# Schematic_Thesis.net
KiCad netlist of a schematic drawn in Altium Designer
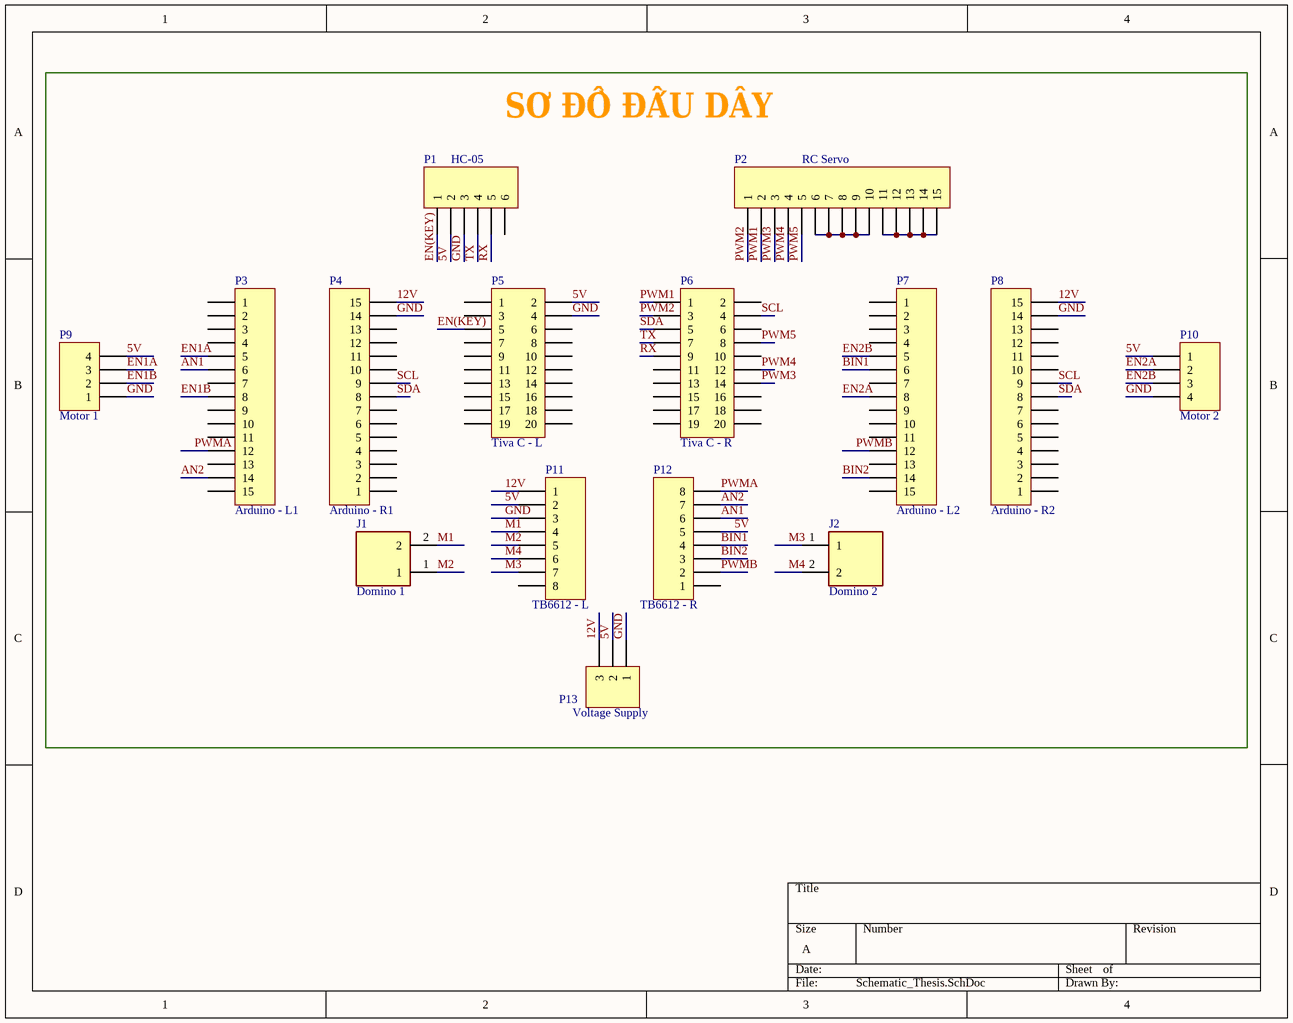
[diagram p0: Schematic_Thesis.SchDoc]

(export (version "E")
  (design (tool "Eeschema 10.0.6"))
  (components
    (comp (ref "J1")
      (value "Domino 1")
      (footprint "KF301-2P:HANDSON_KF301-2P")
      (description "2 Pin Terminal Block 5mm Pitch")
      (fields (field (name "MP") "KF301-2P") (field (name "MF") "Handson Technology"))
      (libsource (lib "") (part "KF301-2P_1"))
    )
    (comp (ref "J2")
      (value "Domino 2")
      (footprint "KF301-2P:HANDSON_KF301-2P")
      (description "2 Pin Terminal Block 5mm Pitch")
      (fields (field (name "MP") "KF301-2P") (field (name "MF") "Handson Technology"))
      (libsource (lib "KF301-2P") (part "KF301-2P"))
    )
    (comp (ref "P1")
      (value "HC-05")
      (footprint "HDR1X6")
      (description "Header, 6-Pin")
      (fields (field (name "PUBLISHER") "Altium Limited"))
      (libsource (lib "Miscellaneous Connectors") (part "Header 6"))
    )
    (comp (ref "P2")
      (value "RC Servo")
      (footprint "HDR1X15")
      (description "Header, 15-Pin")
      (fields (field (name "PUBLISHER") "Altium Limited"))
      (libsource (lib "") (part "Header 15_2"))
    )
    (comp (ref "P3")
      (value "Arduino - L1")
      (footprint "HDR1X15")
      (description "Header, 15-Pin")
      (fields (field (name "PUBLISHER") "Altium Limited"))
      (libsource (lib "Miscellaneous Connectors") (part "Header 15"))
    )
    (comp (ref "P4")
      (value "Arduino - R1")
      (footprint "HDR1X15")
      (description "Header, 15-Pin")
      (fields (field (name "PUBLISHER") "Altium Limited"))
      (libsource (lib "") (part "Header 15_1"))
    )
    (comp (ref "P5")
      (value "Tiva C - L")
      (footprint "HDR2X10")
      (description "Header, 10-Pin, Dual row")
      (fields (field (name "PUBLISHER") "Altium Limited"))
      (libsource (lib "Miscellaneous Connectors") (part "Header 10X2"))
    )
    (comp (ref "P6")
      (value "Tiva C - R")
      (footprint "HDR2X10")
      (description "Header, 10-Pin, Dual row")
      (fields (field (name "PUBLISHER") "Altium Limited"))
      (libsource (lib "Miscellaneous Connectors") (part "Header 10X2"))
    )
    (comp (ref "P7")
      (value "Arduino - L2")
      (footprint "HDR1X15")
      (description "Header, 15-Pin")
      (fields (field (name "PUBLISHER") "Altium Limited"))
      (libsource (lib "Miscellaneous Connectors") (part "Header 15"))
    )
    (comp (ref "P8")
      (value "Arduino - R2")
      (footprint "HDR1X15")
      (description "Header, 15-Pin")
      (fields (field (name "PUBLISHER") "Altium Limited"))
      (libsource (lib "") (part "Header 15_1"))
    )
    (comp (ref "P9")
      (value "Motor 1")
      (footprint "HDR1X4")
      (description "Header, 4-Pin")
      (fields (field (name "PUBLISHER") "Altium Limited"))
      (libsource (lib "Miscellaneous Connectors") (part "Header 4"))
    )
    (comp (ref "P10")
      (value "Motor 2")
      (footprint "HDR1X4")
      (description "Header, 4-Pin")
      (fields (field (name "PUBLISHER") "Altium Limited"))
      (libsource (lib "") (part "Header 4_1"))
    )
    (comp (ref "P11")
      (value "TB6612 - L")
      (footprint "HDR1X8")
      (description "Header, 8-Pin")
      (fields (field (name "PUBLISHER") "Altium Limited"))
      (libsource (lib "") (part "Header 8_1"))
    )
    (comp (ref "P12")
      (value "TB6612 - R")
      (footprint "HDR1X8")
      (description "Header, 8-Pin")
      (fields (field (name "PUBLISHER") "Altium Limited"))
      (libsource (lib "Miscellaneous Connectors") (part "Header 8"))
    )
    (comp (ref "P13")
      (value "Voltage Supply")
      (footprint "HDR1X3")
      (description "Header, 3-Pin")
      (fields (field (name "PUBLISHER") "Altium Limited"))
      (libsource (lib "Miscellaneous Connectors") (part "Header 3"))
    )
  )
  (nets
    (net (code "1") (name "/5V") (class "Default")
      (node (ref "P1") (pin "2") (pinfunction "2_2") (pintype "passive"))
      (node (ref "P10") (pin "1") (pinfunction "1_1") (pintype "passive"))
      (node (ref "P11") (pin "2") (pinfunction "2_2") (pintype "passive"))
      (node (ref "P12") (pin "5") (pinfunction "5_5") (pintype "passive"))
      (node (ref "P13") (pin "2") (pinfunction "2_2") (pintype "passive"))
      (node (ref "P5") (pin "2") (pinfunction "2_2") (pintype "passive"))
      (node (ref "P9") (pin "4") (pinfunction "4_4") (pintype "passive"))
    )
    (net (code "2") (name "/12V") (class "Default")
      (node (ref "P11") (pin "1") (pinfunction "1_1") (pintype "passive"))
      (node (ref "P13") (pin "3") (pinfunction "3_3") (pintype "passive"))
      (node (ref "P4") (pin "15") (pinfunction "15_15") (pintype "passive"))
      (node (ref "P8") (pin "15") (pinfunction "15_15") (pintype "passive"))
    )
    (net (code "3") (name "/AN1") (class "Default")
      (node (ref "P12") (pin "6") (pinfunction "6_6") (pintype "passive"))
      (node (ref "P3") (pin "6") (pinfunction "6_6") (pintype "passive"))
    )
    (net (code "4") (name "/AN2") (class "Default")
      (node (ref "P12") (pin "7") (pinfunction "7_7") (pintype "passive"))
      (node (ref "P3") (pin "14") (pinfunction "14_14") (pintype "passive"))
    )
    (net (code "5") (name "/BIN1") (class "Default")
      (node (ref "P12") (pin "4") (pinfunction "4_4") (pintype "passive"))
      (node (ref "P7") (pin "6") (pinfunction "6_6") (pintype "passive"))
    )
    (net (code "6") (name "/BIN2") (class "Default")
      (node (ref "P12") (pin "3") (pinfunction "3_3") (pintype "passive"))
      (node (ref "P7") (pin "14") (pinfunction "14_14") (pintype "passive"))
    )
    (net (code "7") (name "/EN(KEY)") (class "Default")
      (node (ref "P1") (pin "1") (pinfunction "1_1") (pintype "passive"))
      (node (ref "P5") (pin "5") (pinfunction "5_5") (pintype "passive"))
    )
    (net (code "8") (name "/EN1A") (class "Default")
      (node (ref "P3") (pin "5") (pinfunction "5_5") (pintype "passive"))
      (node (ref "P9") (pin "3") (pinfunction "3_3") (pintype "passive"))
    )
    (net (code "9") (name "/EN1B") (class "Default")
      (node (ref "P3") (pin "8") (pinfunction "8_8") (pintype "passive"))
      (node (ref "P9") (pin "2") (pinfunction "2_2") (pintype "passive"))
    )
    (net (code "10") (name "/EN2A") (class "Default")
      (node (ref "P10") (pin "2") (pinfunction "2_2") (pintype "passive"))
      (node (ref "P7") (pin "8") (pinfunction "8_8") (pintype "passive"))
    )
    (net (code "11") (name "/EN2B") (class "Default")
      (node (ref "P10") (pin "3") (pinfunction "3_3") (pintype "passive"))
      (node (ref "P7") (pin "5") (pinfunction "5_5") (pintype "passive"))
    )
    (net (code "12") (name "/GND") (class "Default")
      (node (ref "P1") (pin "3") (pinfunction "3_3") (pintype "passive"))
      (node (ref "P10") (pin "4") (pinfunction "4_4") (pintype "passive"))
      (node (ref "P11") (pin "3") (pinfunction "3_3") (pintype "passive"))
      (node (ref "P13") (pin "1") (pinfunction "1_1") (pintype "passive"))
      (node (ref "P4") (pin "14") (pinfunction "14_14") (pintype "passive"))
      (node (ref "P5") (pin "4") (pinfunction "4_4") (pintype "passive"))
      (node (ref "P8") (pin "14") (pinfunction "14_14") (pintype "passive"))
      (node (ref "P9") (pin "1") (pinfunction "1_1") (pintype "passive"))
    )
    (net (code "13") (name "/M1") (class "Default")
      (node (ref "J1") (pin "2") (pinfunction "2_2") (pintype "passive"))
      (node (ref "P11") (pin "4") (pinfunction "4_4") (pintype "passive"))
    )
    (net (code "14") (name "/M2") (class "Default")
      (node (ref "J1") (pin "1") (pinfunction "1_1") (pintype "passive"))
      (node (ref "P11") (pin "5") (pinfunction "5_5") (pintype "passive"))
    )
    (net (code "15") (name "/M3") (class "Default")
      (node (ref "J2") (pin "1") (pinfunction "1_1") (pintype "passive"))
      (node (ref "P11") (pin "7") (pinfunction "7_7") (pintype "passive"))
    )
    (net (code "16") (name "/M4") (class "Default")
      (node (ref "J2") (pin "2") (pinfunction "2_2") (pintype "passive"))
      (node (ref "P11") (pin "6") (pinfunction "6_6") (pintype "passive"))
    )
    (net (code "17") (name "/PWM1") (class "Default")
      (node (ref "P2") (pin "2") (pinfunction "2_2") (pintype "passive"))
      (node (ref "P6") (pin "1") (pinfunction "1_1") (pintype "passive"))
    )
    (net (code "18") (name "/PWM2") (class "Default")
      (node (ref "P2") (pin "1") (pinfunction "1_1") (pintype "passive"))
      (node (ref "P6") (pin "3") (pinfunction "3_3") (pintype "passive"))
    )
    (net (code "19") (name "/PWM3") (class "Default")
      (node (ref "P2") (pin "3") (pinfunction "3_3") (pintype "passive"))
      (node (ref "P6") (pin "14") (pinfunction "14_14") (pintype "passive"))
    )
    (net (code "20") (name "/PWM4") (class "Default")
      (node (ref "P2") (pin "4") (pinfunction "4_4") (pintype "passive"))
      (node (ref "P6") (pin "12") (pinfunction "12_12") (pintype "passive"))
    )
    (net (code "21") (name "/PWM5") (class "Default")
      (node (ref "P2") (pin "5") (pinfunction "5_5") (pintype "passive"))
      (node (ref "P6") (pin "8") (pinfunction "8_8") (pintype "passive"))
    )
    (net (code "22") (name "/PWMA") (class "Default")
      (node (ref "P12") (pin "8") (pinfunction "8_8") (pintype "passive"))
      (node (ref "P3") (pin "12") (pinfunction "12_12") (pintype "passive"))
    )
    (net (code "23") (name "/PWMB") (class "Default")
      (node (ref "P12") (pin "2") (pinfunction "2_2") (pintype "passive"))
      (node (ref "P7") (pin "12") (pinfunction "12_12") (pintype "passive"))
    )
    (net (code "24") (name "/RX") (class "Default")
      (node (ref "P1") (pin "5") (pinfunction "5_5") (pintype "passive"))
      (node (ref "P6") (pin "9") (pinfunction "9_9") (pintype "passive"))
    )
    (net (code "25") (name "/SCL") (class "Default")
      (node (ref "P4") (pin "9") (pinfunction "9_9") (pintype "passive"))
      (node (ref "P6") (pin "4") (pinfunction "4_4") (pintype "passive"))
      (node (ref "P8") (pin "9") (pinfunction "9_9") (pintype "passive"))
    )
    (net (code "26") (name "/SDA") (class "Default")
      (node (ref "P4") (pin "8") (pinfunction "8_8") (pintype "passive"))
      (node (ref "P6") (pin "5") (pinfunction "5_5") (pintype "passive"))
      (node (ref "P8") (pin "8") (pinfunction "8_8") (pintype "passive"))
    )
    (net (code "27") (name "/TX") (class "Default")
      (node (ref "P1") (pin "4") (pinfunction "4_4") (pintype "passive"))
      (node (ref "P6") (pin "7") (pinfunction "7_7") (pintype "passive"))
    )
    (net (code "28") (name "Net-(P2-Pad10)") (class "Default")
      (node (ref "P2") (pin "10") (pinfunction "10_10") (pintype "passive"))
      (node (ref "P2") (pin "6") (pinfunction "6_6") (pintype "passive"))
      (node (ref "P2") (pin "7") (pinfunction "7_7") (pintype "passive"))
      (node (ref "P2") (pin "8") (pinfunction "8_8") (pintype "passive"))
      (node (ref "P2") (pin "9") (pinfunction "9_9") (pintype "passive"))
    )
    (net (code "29") (name "Net-(P2-Pad11)") (class "Default")
      (node (ref "P2") (pin "11") (pinfunction "11_11") (pintype "passive"))
      (node (ref "P2") (pin "12") (pinfunction "12_12") (pintype "passive"))
      (node (ref "P2") (pin "13") (pinfunction "13_13") (pintype "passive"))
      (node (ref "P2") (pin "14") (pinfunction "14_14") (pintype "passive"))
      (node (ref "P2") (pin "15") (pinfunction "15_15") (pintype "passive"))
    )
    (net (code "30") (name "unconnected-(P1-Pad6)") (class "Default")
      (node (ref "P1") (pin "6") (pinfunction "6_6") (pintype "passive"))
    )
    (net (code "31") (name "unconnected-(P3-Pad1)") (class "Default")
      (node (ref "P3") (pin "1") (pinfunction "1_1") (pintype "passive"))
    )
    (net (code "32") (name "unconnected-(P3-Pad2)") (class "Default")
      (node (ref "P3") (pin "2") (pinfunction "2_2") (pintype "passive"))
    )
    (net (code "33") (name "unconnected-(P3-Pad3)") (class "Default")
      (node (ref "P3") (pin "3") (pinfunction "3_3") (pintype "passive"))
    )
    (net (code "34") (name "unconnected-(P3-Pad4)") (class "Default")
      (node (ref "P3") (pin "4") (pinfunction "4_4") (pintype "passive"))
    )
    (net (code "35") (name "unconnected-(P3-Pad7)") (class "Default")
      (node (ref "P3") (pin "7") (pinfunction "7_7") (pintype "passive"))
    )
    (net (code "36") (name "unconnected-(P3-Pad9)") (class "Default")
      (node (ref "P3") (pin "9") (pinfunction "9_9") (pintype "passive"))
    )
    (net (code "37") (name "unconnected-(P3-Pad10)") (class "Default")
      (node (ref "P3") (pin "10") (pinfunction "10_10") (pintype "passive"))
    )
    (net (code "38") (name "unconnected-(P3-Pad11)") (class "Default")
      (node (ref "P3") (pin "11") (pinfunction "11_11") (pintype "passive"))
    )
    (net (code "39") (name "unconnected-(P3-Pad13)") (class "Default")
      (node (ref "P3") (pin "13") (pinfunction "13_13") (pintype "passive"))
    )
    (net (code "40") (name "unconnected-(P3-Pad15)") (class "Default")
      (node (ref "P3") (pin "15") (pinfunction "15_15") (pintype "passive"))
    )
    (net (code "41") (name "unconnected-(P4-Pad1)") (class "Default")
      (node (ref "P4") (pin "1") (pinfunction "1_1") (pintype "passive"))
    )
    (net (code "42") (name "unconnected-(P4-Pad2)") (class "Default")
      (node (ref "P4") (pin "2") (pinfunction "2_2") (pintype "passive"))
    )
    (net (code "43") (name "unconnected-(P4-Pad3)") (class "Default")
      (node (ref "P4") (pin "3") (pinfunction "3_3") (pintype "passive"))
    )
    (net (code "44") (name "unconnected-(P4-Pad4)") (class "Default")
      (node (ref "P4") (pin "4") (pinfunction "4_4") (pintype "passive"))
    )
    (net (code "45") (name "unconnected-(P4-Pad5)") (class "Default")
      (node (ref "P4") (pin "5") (pinfunction "5_5") (pintype "passive"))
    )
    (net (code "46") (name "unconnected-(P4-Pad6)") (class "Default")
      (node (ref "P4") (pin "6") (pinfunction "6_6") (pintype "passive"))
    )
    (net (code "47") (name "unconnected-(P4-Pad7)") (class "Default")
      (node (ref "P4") (pin "7") (pinfunction "7_7") (pintype "passive"))
    )
    (net (code "48") (name "unconnected-(P4-Pad10)") (class "Default")
      (node (ref "P4") (pin "10") (pinfunction "10_10") (pintype "passive"))
    )
    (net (code "49") (name "unconnected-(P4-Pad11)") (class "Default")
      (node (ref "P4") (pin "11") (pinfunction "11_11") (pintype "passive"))
    )
    (net (code "50") (name "unconnected-(P4-Pad12)") (class "Default")
      (node (ref "P4") (pin "12") (pinfunction "12_12") (pintype "passive"))
    )
    (net (code "51") (name "unconnected-(P4-Pad13)") (class "Default")
      (node (ref "P4") (pin "13") (pinfunction "13_13") (pintype "passive"))
    )
    (net (code "52") (name "unconnected-(P5-Pad1)") (class "Default")
      (node (ref "P5") (pin "1") (pinfunction "1_1") (pintype "passive"))
    )
    (net (code "53") (name "unconnected-(P5-Pad3)") (class "Default")
      (node (ref "P5") (pin "3") (pinfunction "3_3") (pintype "passive"))
    )
    (net (code "54") (name "unconnected-(P5-Pad6)") (class "Default")
      (node (ref "P5") (pin "6") (pinfunction "6_6") (pintype "passive"))
    )
    (net (code "55") (name "unconnected-(P5-Pad7)") (class "Default")
      (node (ref "P5") (pin "7") (pinfunction "7_7") (pintype "passive"))
    )
    (net (code "56") (name "unconnected-(P5-Pad8)") (class "Default")
      (node (ref "P5") (pin "8") (pinfunction "8_8") (pintype "passive"))
    )
    (net (code "57") (name "unconnected-(P5-Pad9)") (class "Default")
      (node (ref "P5") (pin "9") (pinfunction "9_9") (pintype "passive"))
    )
    (net (code "58") (name "unconnected-(P5-Pad10)") (class "Default")
      (node (ref "P5") (pin "10") (pinfunction "10_10") (pintype "passive"))
    )
    (net (code "59") (name "unconnected-(P5-Pad11)") (class "Default")
      (node (ref "P5") (pin "11") (pinfunction "11_11") (pintype "passive"))
    )
    (net (code "60") (name "unconnected-(P5-Pad12)") (class "Default")
      (node (ref "P5") (pin "12") (pinfunction "12_12") (pintype "passive"))
    )
    (net (code "61") (name "unconnected-(P5-Pad13)") (class "Default")
      (node (ref "P5") (pin "13") (pinfunction "13_13") (pintype "passive"))
    )
    (net (code "62") (name "unconnected-(P5-Pad14)") (class "Default")
      (node (ref "P5") (pin "14") (pinfunction "14_14") (pintype "passive"))
    )
    (net (code "63") (name "unconnected-(P5-Pad15)") (class "Default")
      (node (ref "P5") (pin "15") (pinfunction "15_15") (pintype "passive"))
    )
    (net (code "64") (name "unconnected-(P5-Pad16)") (class "Default")
      (node (ref "P5") (pin "16") (pinfunction "16_16") (pintype "passive"))
    )
    (net (code "65") (name "unconnected-(P5-Pad17)") (class "Default")
      (node (ref "P5") (pin "17") (pinfunction "17_17") (pintype "passive"))
    )
    (net (code "66") (name "unconnected-(P5-Pad18)") (class "Default")
      (node (ref "P5") (pin "18") (pinfunction "18_18") (pintype "passive"))
    )
    (net (code "67") (name "unconnected-(P5-Pad19)") (class "Default")
      (node (ref "P5") (pin "19") (pinfunction "19_19") (pintype "passive"))
    )
    (net (code "68") (name "unconnected-(P5-Pad20)") (class "Default")
      (node (ref "P5") (pin "20") (pinfunction "20_20") (pintype "passive"))
    )
    (net (code "69") (name "unconnected-(P6-Pad2)") (class "Default")
      (node (ref "P6") (pin "2") (pinfunction "2_2") (pintype "passive"))
    )
    (net (code "70") (name "unconnected-(P6-Pad6)") (class "Default")
      (node (ref "P6") (pin "6") (pinfunction "6_6") (pintype "passive"))
    )
    (net (code "71") (name "unconnected-(P6-Pad10)") (class "Default")
      (node (ref "P6") (pin "10") (pinfunction "10_10") (pintype "passive"))
    )
    (net (code "72") (name "unconnected-(P6-Pad11)") (class "Default")
      (node (ref "P6") (pin "11") (pinfunction "11_11") (pintype "passive"))
    )
    (net (code "73") (name "unconnected-(P6-Pad13)") (class "Default")
      (node (ref "P6") (pin "13") (pinfunction "13_13") (pintype "passive"))
    )
    (net (code "74") (name "unconnected-(P6-Pad15)") (class "Default")
      (node (ref "P6") (pin "15") (pinfunction "15_15") (pintype "passive"))
    )
    (net (code "75") (name "unconnected-(P6-Pad16)") (class "Default")
      (node (ref "P6") (pin "16") (pinfunction "16_16") (pintype "passive"))
    )
    (net (code "76") (name "unconnected-(P6-Pad17)") (class "Default")
      (node (ref "P6") (pin "17") (pinfunction "17_17") (pintype "passive"))
    )
    (net (code "77") (name "unconnected-(P6-Pad18)") (class "Default")
      (node (ref "P6") (pin "18") (pinfunction "18_18") (pintype "passive"))
    )
    (net (code "78") (name "unconnected-(P6-Pad19)") (class "Default")
      (node (ref "P6") (pin "19") (pinfunction "19_19") (pintype "passive"))
    )
    (net (code "79") (name "unconnected-(P6-Pad20)") (class "Default")
      (node (ref "P6") (pin "20") (pinfunction "20_20") (pintype "passive"))
    )
    (net (code "80") (name "unconnected-(P7-Pad1)") (class "Default")
      (node (ref "P7") (pin "1") (pinfunction "1_1") (pintype "passive"))
    )
    (net (code "81") (name "unconnected-(P7-Pad2)") (class "Default")
      (node (ref "P7") (pin "2") (pinfunction "2_2") (pintype "passive"))
    )
    (net (code "82") (name "unconnected-(P7-Pad3)") (class "Default")
      (node (ref "P7") (pin "3") (pinfunction "3_3") (pintype "passive"))
    )
    (net (code "83") (name "unconnected-(P7-Pad4)") (class "Default")
      (node (ref "P7") (pin "4") (pinfunction "4_4") (pintype "passive"))
    )
    (net (code "84") (name "unconnected-(P7-Pad7)") (class "Default")
      (node (ref "P7") (pin "7") (pinfunction "7_7") (pintype "passive"))
    )
    (net (code "85") (name "unconnected-(P7-Pad9)") (class "Default")
      (node (ref "P7") (pin "9") (pinfunction "9_9") (pintype "passive"))
    )
    (net (code "86") (name "unconnected-(P7-Pad10)") (class "Default")
      (node (ref "P7") (pin "10") (pinfunction "10_10") (pintype "passive"))
    )
    (net (code "87") (name "unconnected-(P7-Pad11)") (class "Default")
      (node (ref "P7") (pin "11") (pinfunction "11_11") (pintype "passive"))
    )
    (net (code "88") (name "unconnected-(P7-Pad13)") (class "Default")
      (node (ref "P7") (pin "13") (pinfunction "13_13") (pintype "passive"))
    )
    (net (code "89") (name "unconnected-(P7-Pad15)") (class "Default")
      (node (ref "P7") (pin "15") (pinfunction "15_15") (pintype "passive"))
    )
    (net (code "90") (name "unconnected-(P8-Pad1)") (class "Default")
      (node (ref "P8") (pin "1") (pinfunction "1_1") (pintype "passive"))
    )
    (net (code "91") (name "unconnected-(P8-Pad2)") (class "Default")
      (node (ref "P8") (pin "2") (pinfunction "2_2") (pintype "passive"))
    )
    (net (code "92") (name "unconnected-(P8-Pad3)") (class "Default")
      (node (ref "P8") (pin "3") (pinfunction "3_3") (pintype "passive"))
    )
    (net (code "93") (name "unconnected-(P8-Pad4)") (class "Default")
      (node (ref "P8") (pin "4") (pinfunction "4_4") (pintype "passive"))
    )
    (net (code "94") (name "unconnected-(P8-Pad5)") (class "Default")
      (node (ref "P8") (pin "5") (pinfunction "5_5") (pintype "passive"))
    )
    (net (code "95") (name "unconnected-(P8-Pad6)") (class "Default")
      (node (ref "P8") (pin "6") (pinfunction "6_6") (pintype "passive"))
    )
    (net (code "96") (name "unconnected-(P8-Pad7)") (class "Default")
      (node (ref "P8") (pin "7") (pinfunction "7_7") (pintype "passive"))
    )
    (net (code "97") (name "unconnected-(P8-Pad10)") (class "Default")
      (node (ref "P8") (pin "10") (pinfunction "10_10") (pintype "passive"))
    )
    (net (code "98") (name "unconnected-(P8-Pad11)") (class "Default")
      (node (ref "P8") (pin "11") (pinfunction "11_11") (pintype "passive"))
    )
    (net (code "99") (name "unconnected-(P8-Pad12)") (class "Default")
      (node (ref "P8") (pin "12") (pinfunction "12_12") (pintype "passive"))
    )
    (net (code "100") (name "unconnected-(P8-Pad13)") (class "Default")
      (node (ref "P8") (pin "13") (pinfunction "13_13") (pintype "passive"))
    )
    (net (code "101") (name "unconnected-(P11-Pad8)") (class "Default")
      (node (ref "P11") (pin "8") (pinfunction "8_8") (pintype "passive"))
    )
    (net (code "102") (name "unconnected-(P12-Pad1)") (class "Default")
      (node (ref "P12") (pin "1") (pinfunction "1_1") (pintype "passive"))
    )
  )
)
